# TYPEC_USB2_0.net
KiCad netlist of a schematic drawn in Altium Designer
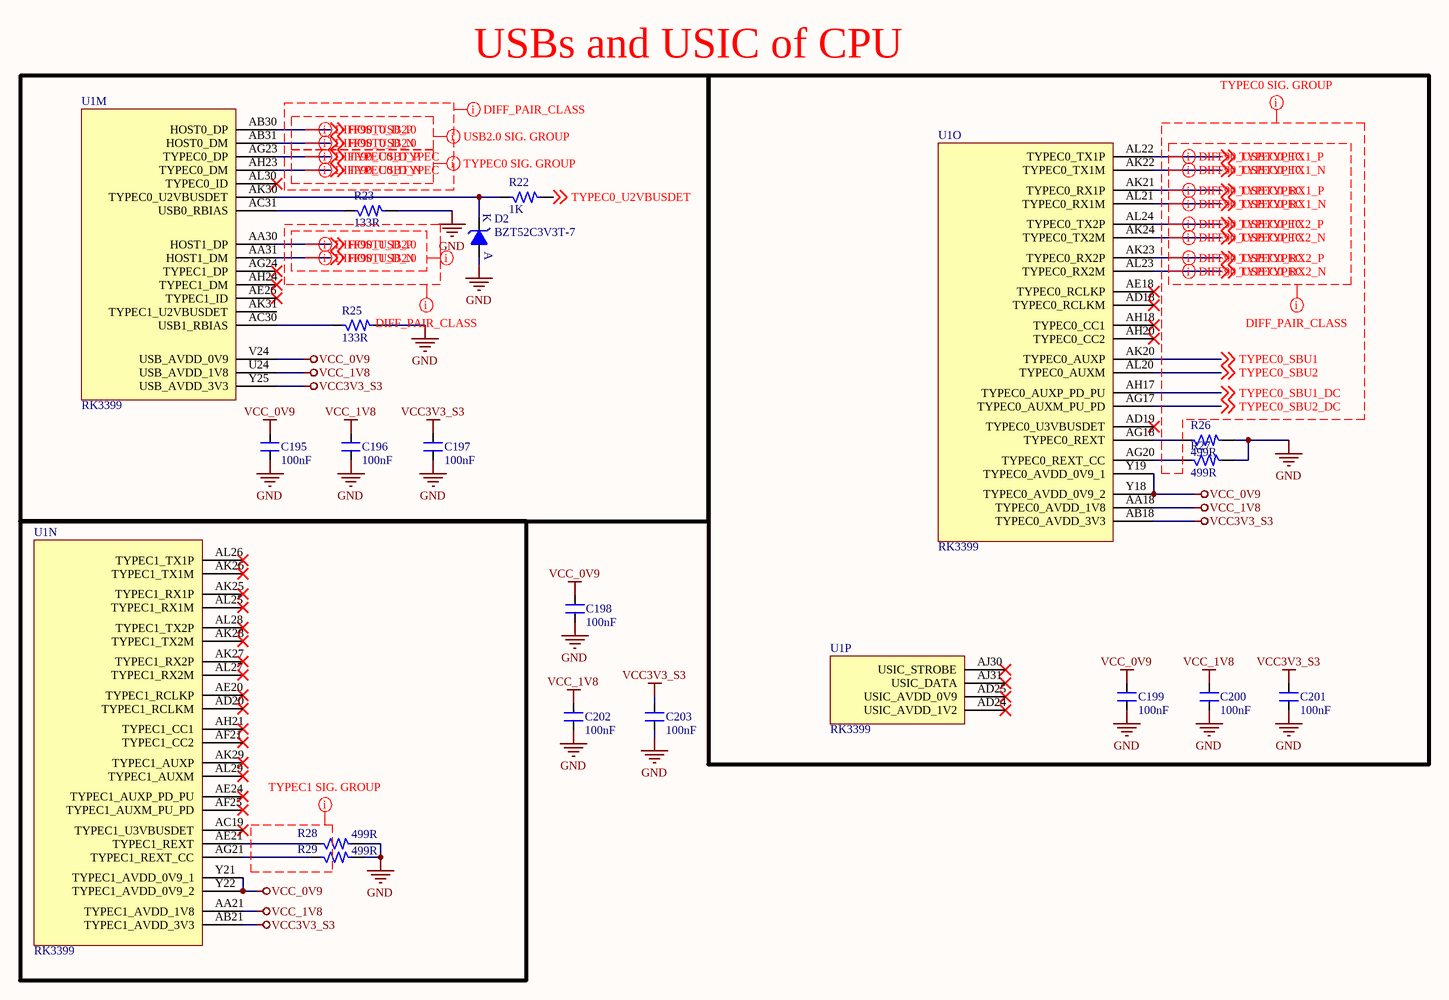
[diagram p0: TYPEC_USB2.0.SchDoc]

(export (version "E")
  (design (tool "Eeschema 10.0.6"))
  (components
    (comp (ref "C195")
      (value "100nF")
      (footprint "CAP_0201")
      (description "0.1µF ±10% 25V Ceramic Capacitor X5R 0201 (0603 Metric)")
      (fields
        (field (name "MANUFACTURER") "TDK Corporation")
        (field (name "MANUFACTURER PART NUMBER") "C0603X5R1E104K030BB")
      )
      (libsource (lib "RK3399 _Module_Intlib") (part "CAP_100nF-25V-10%-0201"))
    )
    (comp (ref "C196")
      (value "100nF")
      (footprint "CAP_0201")
      (description "0.1µF ±10% 25V Ceramic Capacitor X5R 0201 (0603 Metric)")
      (fields
        (field (name "MANUFACTURER") "TDK Corporation")
        (field (name "MANUFACTURER PART NUMBER") "C0603X5R1E104K030BB")
      )
      (libsource (lib "RK3399 _Module_Intlib") (part "CAP_100nF-25V-10%-0201"))
    )
    (comp (ref "C197")
      (value "100nF")
      (footprint "CAP_0201")
      (description "0.1µF ±10% 25V Ceramic Capacitor X5R 0201 (0603 Metric)")
      (fields
        (field (name "MANUFACTURER") "TDK Corporation")
        (field (name "MANUFACTURER PART NUMBER") "C0603X5R1E104K030BB")
      )
      (libsource (lib "RK3399 _Module_Intlib") (part "CAP_100nF-25V-10%-0201"))
    )
    (comp (ref "C198")
      (value "100nF")
      (footprint "CAP_0201")
      (description "0.1µF ±10% 25V Ceramic Capacitor X5R 0201 (0603 Metric)")
      (fields
        (field (name "MANUFACTURER") "TDK Corporation")
        (field (name "MANUFACTURER PART NUMBER") "C0603X5R1E104K030BB")
      )
      (libsource (lib "RK3399 _Module_Intlib") (part "CAP_100nF-25V-10%-0201"))
    )
    (comp (ref "C199")
      (value "100nF")
      (footprint "CAP_0201")
      (description "0.1µF ±10% 25V Ceramic Capacitor X5R 0201 (0603 Metric)")
      (fields
        (field (name "MANUFACTURER") "TDK Corporation")
        (field (name "MANUFACTURER PART NUMBER") "C0603X5R1E104K030BB")
      )
      (libsource (lib "RK3399 _Module_Intlib") (part "CAP_100nF-25V-10%-0201"))
    )
    (comp (ref "C200")
      (value "100nF")
      (footprint "CAP_0201")
      (description "0.1µF ±10% 25V Ceramic Capacitor X5R 0201 (0603 Metric)")
      (fields
        (field (name "MANUFACTURER") "TDK Corporation")
        (field (name "MANUFACTURER PART NUMBER") "C0603X5R1E104K030BB")
      )
      (libsource (lib "RK3399 _Module_Intlib") (part "CAP_100nF-25V-10%-0201"))
    )
    (comp (ref "C201")
      (value "100nF")
      (footprint "CAP_0201")
      (description "0.1µF ±10% 25V Ceramic Capacitor X5R 0201 (0603 Metric)")
      (fields
        (field (name "MANUFACTURER") "TDK Corporation")
        (field (name "MANUFACTURER PART NUMBER") "C0603X5R1E104K030BB")
      )
      (libsource (lib "RK3399 _Module_Intlib") (part "CAP_100nF-25V-10%-0201"))
    )
    (comp (ref "C202")
      (value "100nF")
      (footprint "CAP_0201")
      (description "0.1µF ±10% 25V Ceramic Capacitor X5R 0201 (0603 Metric)")
      (fields
        (field (name "MANUFACTURER") "TDK Corporation")
        (field (name "MANUFACTURER PART NUMBER") "C0603X5R1E104K030BB")
      )
      (libsource (lib "RK3399 _Module_Intlib") (part "CAP_100nF-25V-10%-0201"))
    )
    (comp (ref "C203")
      (value "100nF")
      (footprint "CAP_0201")
      (description "0.1µF ±10% 25V Ceramic Capacitor X5R 0201 (0603 Metric)")
      (fields
        (field (name "MANUFACTURER") "TDK Corporation")
        (field (name "MANUFACTURER PART NUMBER") "C0603X5R1E104K030BB")
      )
      (libsource (lib "RK3399 _Module_Intlib") (part "CAP_100nF-25V-10%-0201"))
    )
    (comp (ref "D2")
      (value "BZT52C3V3T-7")
      (footprint "DIO_SOD523")
      (description "Zener Diode 3.3V 300mW ±6% Surface Mount SOD-523")
      (fields (field (name "MANUFACTURER") "Diodes Incorporated"))
      (libsource (lib "RK3399 _Module_Schlib") (part "DIO-Z_3.3V-300mW-SOD-523"))
    )
    (comp (ref "R22")
      (value "1K")
      (footprint "RES_0201")
      (description "1 kOhms ±1% 0.05W, 1/20W Chip Resistor 0201 (0603 Metric) Thick Film")
      (fields
        (field (name "MANUFACTURER") "Yageo")
        (field (name "MANUFACTURER PART NUMBER") "RC0201FR-071KL")
      )
      (libsource (lib "RK3399 _Module_Intlib") (part "RES_1K-0.05W-1%-0201"))
    )
    (comp (ref "R23")
      (value "133R")
      (footprint "RES_0201")
      (description "133 Ohms ±1% 0.05W, 1/20W Chip Resistor 0201 (0603 Metric) Automotive AEC-Q200 Thick Film")
      (fields
        (field (name "MANUFACTURER") "Panasonic Electronic Components")
        (field (name "MANUFACTURER PART NUMBER") "ERJ-1GNF1330C")
      )
      (libsource (lib "RK3399 _Module_Intlib") (part "RES_133R-0.05W-1%-0201"))
    )
    (comp (ref "R25")
      (value "133R")
      (footprint "RES_0201")
      (description "133 Ohms ±1% 0.05W, 1/20W Chip Resistor 0201 (0603 Metric) Automotive AEC-Q200 Thick Film")
      (fields
        (field (name "MANUFACTURER") "Panasonic Electronic Components")
        (field (name "MANUFACTURER PART NUMBER") "ERJ-1GNF1330C")
      )
      (libsource (lib "RK3399 _Module_Intlib") (part "RES_133R-0.05W-1%-0201"))
    )
    (comp (ref "R26")
      (value "499R")
      (footprint "RES_0201")
      (description "499 Ohms ±1% 0.05W, 1/20W Chip Resistor 0201 (0603 Metric) Thick Film")
      (fields
        (field (name "MANUFACTURER") "Stackpole Electronics Inc")
        (field (name "MANUFACTURER PART NUMBER") "RMCF0201FT499R")
      )
      (libsource (lib "Toby_Nguyen_Component_Lib") (part "RES_499R-0.05W-1%-0201"))
    )
    (comp (ref "R27")
      (value "499R")
      (footprint "RES_0201")
      (description "499 Ohms ±1% 0.05W, 1/20W Chip Resistor 0201 (0603 Metric) Thick Film")
      (fields
        (field (name "MANUFACTURER") "Stackpole Electronics Inc")
        (field (name "MANUFACTURER PART NUMBER") "RMCF0201FT499R")
      )
      (libsource (lib "RK3399 _Module_Intlib") (part "RES_499R-0.05W-1%-0201"))
    )
    (comp (ref "R28")
      (value "499R")
      (footprint "RES_0201")
      (description "499 Ohms ±1% 0.05W, 1/20W Chip Resistor 0201 (0603 Metric) Thick Film")
      (fields
        (field (name "MANUFACTURER") "Stackpole Electronics Inc")
        (field (name "MANUFACTURER PART NUMBER") "RMCF0201FT499R")
      )
      (libsource (lib "RK3399 _Module_Intlib") (part "RES_499R-0.05W-1%-0201"))
    )
    (comp (ref "R29")
      (value "499R")
      (footprint "RES_0201")
      (description "499 Ohms ±1% 0.05W, 1/20W Chip Resistor 0201 (0603 Metric) Thick Film")
      (fields
        (field (name "MANUFACTURER") "Stackpole Electronics Inc")
        (field (name "MANUFACTURER PART NUMBER") "RMCF0201FT499R")
      )
      (libsource (lib "RK3399 _Module_Intlib") (part "RES_499R-0.05W-1%-0201"))
    )
    (comp (ref "U1")
      (value "RK3399")
      (footprint "FBGA828_23_826X826")
      (description "RK3399 is a low power, high performance processor for computing, personal mobile.")
      (fields (field (name "MANUFACTURER") "Rockchip"))
      (libsource (lib "RK3399 _Module_Schlib") (part "IC_RK3399-FCBGA828"))
    )
  )
  (nets
    (net (code "1") (name "GND") (class "Default")
      (node (ref "C195") (pin "2") (pinfunction "2_2") (pintype "passive"))
      (node (ref "C196") (pin "1") (pinfunction "1_1") (pintype "passive"))
      (node (ref "C197") (pin "1") (pinfunction "1_1") (pintype "passive"))
      (node (ref "C198") (pin "1") (pinfunction "1_1") (pintype "passive"))
      (node (ref "C199") (pin "1") (pinfunction "1_1") (pintype "passive"))
      (node (ref "C200") (pin "1") (pinfunction "1_1") (pintype "passive"))
      (node (ref "C201") (pin "1") (pinfunction "1_1") (pintype "passive"))
      (node (ref "C202") (pin "1") (pinfunction "1_1") (pintype "passive"))
      (node (ref "C203") (pin "1") (pinfunction "1_1") (pintype "passive"))
      (node (ref "D2") (pin "A") (pinfunction "A_A") (pintype "passive"))
      (node (ref "R23") (pin "2") (pinfunction "2_2") (pintype "passive"))
      (node (ref "R25") (pin "2") (pinfunction "2_2") (pintype "passive"))
      (node (ref "R26") (pin "2") (pinfunction "2_2") (pintype "passive"))
      (node (ref "R27") (pin "2") (pinfunction "2_2") (pintype "passive"))
      (node (ref "R28") (pin "2") (pinfunction "2_2") (pintype "passive"))
      (node (ref "R29") (pin "2") (pinfunction "2_2") (pintype "passive"))
    )
    (net (code "2") (name "HOST0_D_N") (class "Default")
      (node (ref "U1") (pin "AB31") (pinfunction "HOST0_DM_AB31") (pintype "passive"))
    )
    (net (code "3") (name "HOST0_D_P") (class "Default")
      (node (ref "U1") (pin "AB30") (pinfunction "HOST0_DP_AB30") (pintype "passive"))
    )
    (net (code "4") (name "HOST1_D_N") (class "Default")
      (node (ref "U1") (pin "AA31") (pinfunction "HOST1_DM_AA31") (pintype "passive"))
    )
    (net (code "5") (name "HOST1_D_P") (class "Default")
      (node (ref "U1") (pin "AA30") (pinfunction "HOST1_DP_AA30") (pintype "passive"))
    )
    (net (code "6") (name "Net-(U1M-TYPEC0_U2VBUSDET)") (class "Default")
      (node (ref "D2") (pin "K") (pinfunction "K_K") (pintype "passive"))
      (node (ref "R22") (pin "1") (pinfunction "1_1") (pintype "passive"))
      (node (ref "U1") (pin "AK30") (pinfunction "TYPEC0_U2VBUSDET_AK30") (pintype "passive"))
    )
    (net (code "7") (name "Net-(U1M-USB0_RBIAS)") (class "Default")
      (node (ref "R23") (pin "1") (pinfunction "1_1") (pintype "passive"))
      (node (ref "U1") (pin "AC31") (pinfunction "USB0_RBIAS_AC31") (pintype "passive"))
    )
    (net (code "8") (name "Net-(U1M-USB1_RBIAS)") (class "Default")
      (node (ref "R25") (pin "1") (pinfunction "1_1") (pintype "passive"))
      (node (ref "U1") (pin "AC30") (pinfunction "USB1_RBIAS_AC30") (pintype "passive"))
    )
    (net (code "9") (name "Net-(U1N-TYPEC1_REXT)") (class "Default")
      (node (ref "R28") (pin "1") (pinfunction "1_1") (pintype "passive"))
      (node (ref "U1") (pin "AE21") (pinfunction "TYPEC1_REXT_AE21") (pintype "passive"))
    )
    (net (code "10") (name "Net-(U1N-TYPEC1_REXT_CC)") (class "Default")
      (node (ref "R29") (pin "1") (pinfunction "1_1") (pintype "passive"))
      (node (ref "U1") (pin "AG21") (pinfunction "TYPEC1_REXT_CC_AG21") (pintype "passive"))
    )
    (net (code "11") (name "Net-(U1O-TYPEC0_REXT)") (class "Default")
      (node (ref "R26") (pin "1") (pinfunction "1_1") (pintype "passive"))
      (node (ref "U1") (pin "AG18") (pinfunction "TYPEC0_REXT_AG18") (pintype "passive"))
    )
    (net (code "12") (name "Net-(U1O-TYPEC0_REXT_CC)") (class "Default")
      (node (ref "R27") (pin "1") (pinfunction "1_1") (pintype "passive"))
      (node (ref "U1") (pin "AG20") (pinfunction "TYPEC0_REXT_CC_AG20") (pintype "passive"))
    )
    (net (code "13") (name "TYPEC0_D_N") (class "Default")
      (node (ref "U1") (pin "AH23") (pinfunction "TYPEC0_DM_AH23") (pintype "passive"))
    )
    (net (code "14") (name "TYPEC0_D_P") (class "Default")
      (node (ref "U1") (pin "AG23") (pinfunction "TYPEC0_DP_AG23") (pintype "passive"))
    )
    (net (code "15") (name "TYPEC0_RX1_N") (class "Default")
      (node (ref "U1") (pin "AL21") (pinfunction "TYPEC0_RX1M_AL21") (pintype "passive"))
    )
    (net (code "16") (name "TYPEC0_RX1_P") (class "Default")
      (node (ref "U1") (pin "AK21") (pinfunction "TYPEC0_RX1P_AK21") (pintype "passive"))
    )
    (net (code "17") (name "TYPEC0_RX2_N") (class "Default")
      (node (ref "U1") (pin "AL23") (pinfunction "TYPEC0_RX2M_AL23") (pintype "passive"))
    )
    (net (code "18") (name "TYPEC0_RX2_P") (class "Default")
      (node (ref "U1") (pin "AK23") (pinfunction "TYPEC0_RX2P_AK23") (pintype "passive"))
    )
    (net (code "19") (name "TYPEC0_SBU1") (class "Default")
      (node (ref "U1") (pin "AK20") (pinfunction "TYPEC0_AUXP_AK20") (pintype "passive"))
    )
    (net (code "20") (name "TYPEC0_SBU1_DC") (class "Default")
      (node (ref "U1") (pin "AH17") (pinfunction "TYPEC0_AUXP_PD_PU_AH17") (pintype "passive"))
    )
    (net (code "21") (name "TYPEC0_SBU2") (class "Default")
      (node (ref "U1") (pin "AL20") (pinfunction "TYPEC0_AUXM_AL20") (pintype "passive"))
    )
    (net (code "22") (name "TYPEC0_SBU2_DC") (class "Default")
      (node (ref "U1") (pin "AG17") (pinfunction "TYPEC0_AUXM_PU_PD_AG17") (pintype "passive"))
    )
    (net (code "23") (name "TYPEC0_TX1_N") (class "Default")
      (node (ref "U1") (pin "AK22") (pinfunction "TYPEC0_TX1M_AK22") (pintype "passive"))
    )
    (net (code "24") (name "TYPEC0_TX1_P") (class "Default")
      (node (ref "U1") (pin "AL22") (pinfunction "TYPEC0_TX1P_AL22") (pintype "passive"))
    )
    (net (code "25") (name "TYPEC0_TX2_N") (class "Default")
      (node (ref "U1") (pin "AK24") (pinfunction "TYPEC0_TX2M_AK24") (pintype "passive"))
    )
    (net (code "26") (name "TYPEC0_TX2_P") (class "Default")
      (node (ref "U1") (pin "AL24") (pinfunction "TYPEC0_TX2P_AL24") (pintype "passive"))
    )
    (net (code "27") (name "TYPEC0_U2VBUSDET") (class "Default")
      (node (ref "R22") (pin "2") (pinfunction "2_2") (pintype "passive"))
    )
    (net (code "28") (name "VCC3V3_S3") (class "Default")
      (node (ref "C197") (pin "2") (pinfunction "2_2") (pintype "passive"))
      (node (ref "C201") (pin "2") (pinfunction "2_2") (pintype "passive"))
      (node (ref "C203") (pin "2") (pinfunction "2_2") (pintype "passive"))
      (node (ref "U1") (pin "AB18") (pinfunction "TYPEC0_AVDD_3V3_AB18") (pintype "passive"))
      (node (ref "U1") (pin "AB21") (pinfunction "TYPEC1_AVDD_3V3_AB21") (pintype "passive"))
      (node (ref "U1") (pin "Y25") (pinfunction "USB_AVDD_3V3_Y25") (pintype "passive"))
    )
    (net (code "29") (name "VCC_0V9") (class "Default")
      (node (ref "C195") (pin "1") (pinfunction "1_1") (pintype "passive"))
      (node (ref "C198") (pin "2") (pinfunction "2_2") (pintype "passive"))
      (node (ref "C199") (pin "2") (pinfunction "2_2") (pintype "passive"))
      (node (ref "U1") (pin "V24") (pinfunction "USB_AVDD_0V9_V24") (pintype "passive"))
      (node (ref "U1") (pin "Y18") (pinfunction "TYPEC0_AVDD_0V9_2_Y18") (pintype "passive"))
      (node (ref "U1") (pin "Y19") (pinfunction "TYPEC0_AVDD_0V9_1_Y19") (pintype "passive"))
      (node (ref "U1") (pin "Y21") (pinfunction "TYPEC1_AVDD_0V9_1_Y21") (pintype "passive"))
      (node (ref "U1") (pin "Y22") (pinfunction "TYPEC1_AVDD_0V9_2_Y22") (pintype "passive"))
    )
    (net (code "30") (name "VCC_1V8") (class "Default")
      (node (ref "C196") (pin "2") (pinfunction "2_2") (pintype "passive"))
      (node (ref "C200") (pin "2") (pinfunction "2_2") (pintype "passive"))
      (node (ref "C202") (pin "2") (pinfunction "2_2") (pintype "passive"))
      (node (ref "U1") (pin "AA18") (pinfunction "TYPEC0_AVDD_1V8_AA18") (pintype "passive"))
      (node (ref "U1") (pin "AA21") (pinfunction "TYPEC1_AVDD_1V8_AA21") (pintype "passive"))
      (node (ref "U1") (pin "U24") (pinfunction "USB_AVDD_1V8_U24") (pintype "passive"))
    )
    (net (code "31") (name "unconnected-(U1M-TYPEC0_ID-PadAL30)") (class "Default")
      (node (ref "U1") (pin "AL30") (pinfunction "TYPEC0_ID_AL30") (pintype "passive+no_connect"))
    )
    (net (code "32") (name "unconnected-(U1M-TYPEC1_DM-PadAH24)") (class "Default")
      (node (ref "U1") (pin "AH24") (pinfunction "TYPEC1_DM_AH24") (pintype "passive+no_connect"))
    )
    (net (code "33") (name "unconnected-(U1M-TYPEC1_DP-PadAG24)") (class "Default")
      (node (ref "U1") (pin "AG24") (pinfunction "TYPEC1_DP_AG24") (pintype "passive+no_connect"))
    )
    (net (code "34") (name "unconnected-(U1M-TYPEC1_ID-PadAE26)") (class "Default")
      (node (ref "U1") (pin "AE26") (pinfunction "TYPEC1_ID_AE26") (pintype "passive+no_connect"))
    )
    (net (code "35") (name "unconnected-(U1M-TYPEC1_U2VBUSDET-PadAK31)") (class "Default")
      (node (ref "U1") (pin "AK31") (pinfunction "TYPEC1_U2VBUSDET_AK31") (pintype "passive"))
    )
    (net (code "36") (name "unconnected-(U1N-TYPEC1_AUXM-PadAL29)") (class "Default")
      (node (ref "U1") (pin "AL29") (pinfunction "TYPEC1_AUXM_AL29") (pintype "passive+no_connect"))
    )
    (net (code "37") (name "unconnected-(U1N-TYPEC1_AUXM_PU_PD-PadAF25)") (class "Default")
      (node (ref "U1") (pin "AF25") (pinfunction "TYPEC1_AUXM_PU_PD_AF25") (pintype "passive+no_connect"))
    )
    (net (code "38") (name "unconnected-(U1N-TYPEC1_AUXP-PadAK29)") (class "Default")
      (node (ref "U1") (pin "AK29") (pinfunction "TYPEC1_AUXP_AK29") (pintype "passive+no_connect"))
    )
    (net (code "39") (name "unconnected-(U1N-TYPEC1_AUXP_PD_PU-PadAE24)") (class "Default")
      (node (ref "U1") (pin "AE24") (pinfunction "TYPEC1_AUXP_PD_PU_AE24") (pintype "passive+no_connect"))
    )
    (net (code "40") (name "unconnected-(U1N-TYPEC1_CC1-PadAH21)") (class "Default")
      (node (ref "U1") (pin "AH21") (pinfunction "TYPEC1_CC1_AH21") (pintype "passive+no_connect"))
    )
    (net (code "41") (name "unconnected-(U1N-TYPEC1_CC2-PadAF21)") (class "Default")
      (node (ref "U1") (pin "AF21") (pinfunction "TYPEC1_CC2_AF21") (pintype "passive+no_connect"))
    )
    (net (code "42") (name "unconnected-(U1N-TYPEC1_RCLKM-PadAD20)") (class "Default")
      (node (ref "U1") (pin "AD20") (pinfunction "TYPEC1_RCLKM_AD20") (pintype "passive+no_connect"))
    )
    (net (code "43") (name "unconnected-(U1N-TYPEC1_RCLKP-PadAE20)") (class "Default")
      (node (ref "U1") (pin "AE20") (pinfunction "TYPEC1_RCLKP_AE20") (pintype "passive+no_connect"))
    )
    (net (code "44") (name "unconnected-(U1N-TYPEC1_RX1M-PadAL25)") (class "Default")
      (node (ref "U1") (pin "AL25") (pinfunction "TYPEC1_RX1M_AL25") (pintype "passive+no_connect"))
    )
    (net (code "45") (name "unconnected-(U1N-TYPEC1_RX1P-PadAK25)") (class "Default")
      (node (ref "U1") (pin "AK25") (pinfunction "TYPEC1_RX1P_AK25") (pintype "passive+no_connect"))
    )
    (net (code "46") (name "unconnected-(U1N-TYPEC1_RX2M-PadAL27)") (class "Default")
      (node (ref "U1") (pin "AL27") (pinfunction "TYPEC1_RX2M_AL27") (pintype "passive+no_connect"))
    )
    (net (code "47") (name "unconnected-(U1N-TYPEC1_RX2P-PadAK27)") (class "Default")
      (node (ref "U1") (pin "AK27") (pinfunction "TYPEC1_RX2P_AK27") (pintype "passive+no_connect"))
    )
    (net (code "48") (name "unconnected-(U1N-TYPEC1_TX1M-PadAK26)") (class "Default")
      (node (ref "U1") (pin "AK26") (pinfunction "TYPEC1_TX1M_AK26") (pintype "passive+no_connect"))
    )
    (net (code "49") (name "unconnected-(U1N-TYPEC1_TX1P-PadAL26)") (class "Default")
      (node (ref "U1") (pin "AL26") (pinfunction "TYPEC1_TX1P_AL26") (pintype "passive+no_connect"))
    )
    (net (code "50") (name "unconnected-(U1N-TYPEC1_TX2M-PadAK28)") (class "Default")
      (node (ref "U1") (pin "AK28") (pinfunction "TYPEC1_TX2M_AK28") (pintype "passive+no_connect"))
    )
    (net (code "51") (name "unconnected-(U1N-TYPEC1_TX2P-PadAL28)") (class "Default")
      (node (ref "U1") (pin "AL28") (pinfunction "TYPEC1_TX2P_AL28") (pintype "passive+no_connect"))
    )
    (net (code "52") (name "unconnected-(U1N-TYPEC1_U3VBUSDET-PadAC19)") (class "Default")
      (node (ref "U1") (pin "AC19") (pinfunction "TYPEC1_U3VBUSDET_AC19") (pintype "passive+no_connect"))
    )
    (net (code "53") (name "unconnected-(U1O-TYPEC0_CC1-PadAH18)") (class "Default")
      (node (ref "U1") (pin "AH18") (pinfunction "TYPEC0_CC1_AH18") (pintype "passive+no_connect"))
    )
    (net (code "54") (name "unconnected-(U1O-TYPEC0_CC2-PadAH20)") (class "Default")
      (node (ref "U1") (pin "AH20") (pinfunction "TYPEC0_CC2_AH20") (pintype "passive+no_connect"))
    )
    (net (code "55") (name "unconnected-(U1O-TYPEC0_RCLKM-PadAD18)") (class "Default")
      (node (ref "U1") (pin "AD18") (pinfunction "TYPEC0_RCLKM_AD18") (pintype "passive+no_connect"))
    )
    (net (code "56") (name "unconnected-(U1O-TYPEC0_RCLKP-PadAE18)") (class "Default")
      (node (ref "U1") (pin "AE18") (pinfunction "TYPEC0_RCLKP_AE18") (pintype "passive+no_connect"))
    )
    (net (code "57") (name "unconnected-(U1O-TYPEC0_U3VBUSDET-PadAD19)") (class "Default")
      (node (ref "U1") (pin "AD19") (pinfunction "TYPEC0_U3VBUSDET_AD19") (pintype "passive+no_connect"))
    )
    (net (code "58") (name "unconnected-(U1P-USIC_AVDD_0V9-PadAD25)") (class "Default")
      (node (ref "U1") (pin "AD25") (pinfunction "USIC_AVDD_0V9_AD25") (pintype "passive+no_connect"))
    )
    (net (code "59") (name "unconnected-(U1P-USIC_AVDD_1V2-PadAD24)") (class "Default")
      (node (ref "U1") (pin "AD24") (pinfunction "USIC_AVDD_1V2_AD24") (pintype "passive+no_connect"))
    )
    (net (code "60") (name "unconnected-(U1P-USIC_DATA-PadAJ31)") (class "Default")
      (node (ref "U1") (pin "AJ31") (pinfunction "USIC_DATA_AJ31") (pintype "passive+no_connect"))
    )
    (net (code "61") (name "unconnected-(U1P-USIC_STROBE-PadAJ30)") (class "Default")
      (node (ref "U1") (pin "AJ30") (pinfunction "USIC_STROBE_AJ30") (pintype "passive+no_connect"))
    )
  )
)
